# Sheet1.net
KiCad netlist of a schematic drawn in Altium Designer
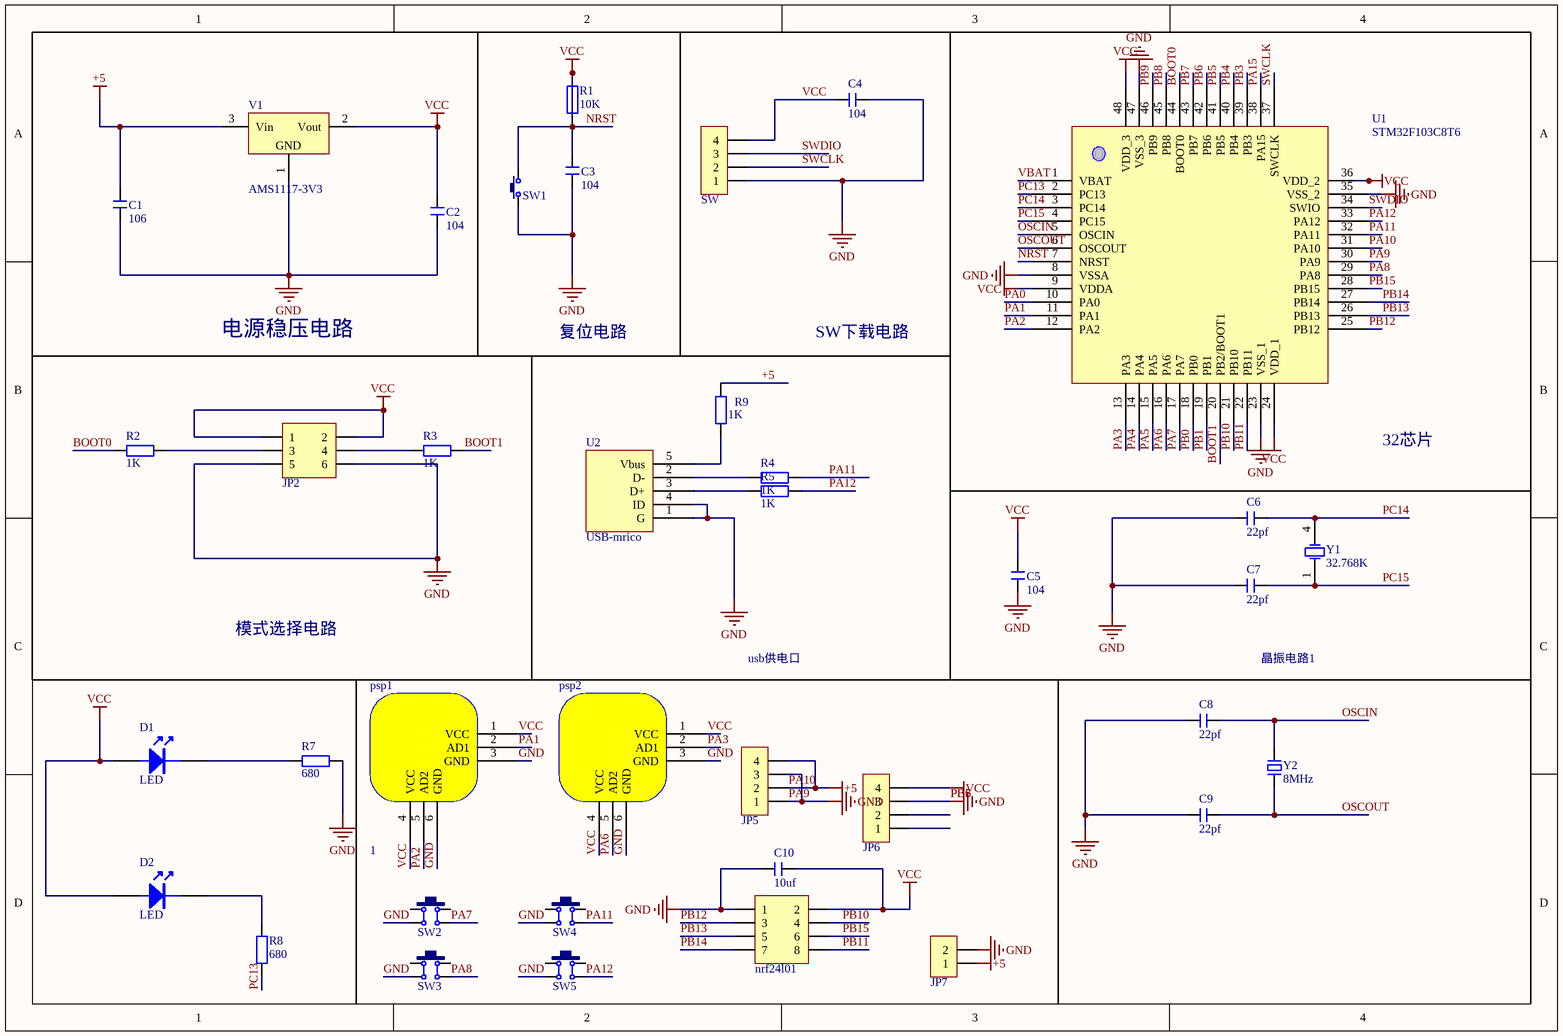
[diagram p0: Sheet1.SchDoc]

(export (version "E")
  (design (tool "Eeschema 10.0.6"))
  (components
    (comp (ref "C1")
      (value "106")
      (footprint "C 0805_L")
      (description "贴片电容")
      (libsource (lib "0.1 - 电阻-电容-电感") (part "C"))
    )
    (comp (ref "C2")
      (value "104")
      (footprint "C 0805_L")
      (description "贴片电容")
      (libsource (lib "0.1 - 电阻-电容-电感") (part "C"))
    )
    (comp (ref "C3")
      (value "104")
      (footprint "C 0805_L")
      (description "贴片电容")
      (libsource (lib "0.1 - 电阻-电容-电感") (part "C"))
    )
    (comp (ref "C4")
      (value "104")
      (footprint "C 0805_L")
      (description "贴片电容")
      (libsource (lib "0.1 - 电阻-电容-电感") (part "C"))
    )
    (comp (ref "C5")
      (value "104")
      (footprint "C 0805_L")
      (description "贴片电容")
      (libsource (lib "0.1 - 电阻-电容-电感") (part "C"))
    )
    (comp (ref "C6")
      (value "22pf")
      (footprint "C 0805_L")
      (description "贴片电容")
      (libsource (lib "0.1 - 电阻-电容-电感") (part "C"))
    )
    (comp (ref "C7")
      (value "22pf")
      (footprint "C 0805_L")
      (description "贴片电容")
      (libsource (lib "0.1 - 电阻-电容-电感") (part "C"))
    )
    (comp (ref "C8")
      (value "22pf")
      (footprint "C 0805_L")
      (description "贴片电容")
      (libsource (lib "0.1 - 电阻-电容-电感") (part "C"))
    )
    (comp (ref "C9")
      (value "22pf")
      (footprint "C 0805_L")
      (description "贴片电容")
      (libsource (lib "0.1 - 电阻-电容-电感") (part "C"))
    )
    (comp (ref "C10")
      (value "10uf")
      (footprint "C 0805_L")
      (description "贴片电容")
      (libsource (lib "0.1 - 电阻-电容-电感") (part "C"))
    )
    (comp (ref "D1") (value "LED") (footprint "LED 0805G") (libsource (lib "stm32原理图库") (part "LED")))
    (comp (ref "D2") (value "LED") (footprint "LED 0805G") (libsource (lib "stm32原理图库") (part "LED")))
    (comp (ref "JP2")
      (value "Header3X2")
      (footprint "HDR2.54-LI-2x3P")
      (description "3*2P接插件")
      (fields (field (name "版权归属") "封装库来自淘宝 ID：黄晶宝石"))
      (libsource (lib "5.3 - 接插件-脚距2.54 (100mil) ") (part "Header 3X2"))
    )
    (comp (ref "JP5")
      (value "HDR-1X4")
      (footprint "HDR2.54-M-LI-4P")
      (description "4P接插件")
      (fields (field (name "版权归属") "封装库来自淘宝 ID：黄晶宝石"))
      (libsource (lib "5.3 - 接插件-脚距2.54 (100mil) ") (part "Header 4"))
    )
    (comp (ref "JP6")
      (value "HDR-1X4")
      (footprint "HDR2.54-M-LI-4P")
      (description "4P接插件")
      (fields (field (name "版权归属") "封装库来自淘宝 ID：黄晶宝石"))
      (libsource (lib "5.3 - 接插件-脚距2.54 (100mil) ") (part "Header 4"))
    )
    (comp (ref "JP7")
      (value "HDR-1X2")
      (footprint "HDR2.54-WI-2P")
      (description "2P接插件")
      (fields (field (name "版权归属") "封装库来自淘宝 ID：黄晶宝石"))
      (libsource (lib "5.3 - 接插件-脚距2.54 (100mil) ") (part "Header 2"))
    )
    (comp (ref "nrf24l01")
      (value "Header 4X2")
      (footprint "HDR2.54-LI-2x4P")
      (description "4*2P接插件")
      (fields (field (name "版权归属") "封装库来自淘宝 ID：黄晶宝石"))
      (libsource (lib "5.3 - 接插件-脚距2.54 (100mil) ") (part "Header 4X2"))
    )
    (comp (ref "psp1") (value "1") (footprint "PSP摇杆") (libsource (lib "PSP摇杆") (part "PSP摇杆")))
    (comp (ref "psp2") (value "~") (footprint "PSP摇杆") (libsource (lib "PSP摇杆") (part "PSP摇杆")))
    (comp (ref "R1")
      (value "10K")
      (footprint "R 0805_L")
      (description "贴片电阻")
      (fields (field (name "版权归属") "来自淘宝 ID：黄晶宝石"))
      (libsource (lib "0.1 - 电阻-电容-电感") (part "R"))
    )
    (comp (ref "R2")
      (value "1K")
      (footprint "R 0805_L")
      (description "贴片电阻")
      (fields (field (name "版权归属") "来自淘宝 ID：黄晶宝石"))
      (libsource (lib "0.1 - 电阻-电容-电感") (part "R"))
    )
    (comp (ref "R3")
      (value "1K")
      (footprint "R 0805_L")
      (description "贴片电阻")
      (fields (field (name "版权归属") "来自淘宝 ID：黄晶宝石"))
      (libsource (lib "0.1 - 电阻-电容-电感") (part "R"))
    )
    (comp (ref "R4")
      (value "1K")
      (footprint "R 0805_L")
      (description "贴片电阻")
      (fields (field (name "版权归属") "来自淘宝 ID：黄晶宝石"))
      (libsource (lib "0.1 - 电阻-电容-电感") (part "R"))
    )
    (comp (ref "R5")
      (value "1K")
      (footprint "R 0805_L")
      (description "贴片电阻")
      (fields (field (name "版权归属") "来自淘宝 ID：黄晶宝石"))
      (libsource (lib "0.1 - 电阻-电容-电感") (part "R"))
    )
    (comp (ref "R7")
      (value "680")
      (footprint "R 0805_L")
      (description "贴片电阻")
      (fields (field (name "版权归属") "来自淘宝 ID：黄晶宝石"))
      (libsource (lib "0.1 - 电阻-电容-电感") (part "R"))
    )
    (comp (ref "R8")
      (value "680")
      (footprint "R 0805_L")
      (description "贴片电阻")
      (fields (field (name "版权归属") "来自淘宝 ID：黄晶宝石"))
      (libsource (lib "0.1 - 电阻-电容-电感") (part "R"))
    )
    (comp (ref "R9")
      (value "1K")
      (footprint "R 0805_L")
      (description "贴片电阻")
      (fields (field (name "版权归属") "来自淘宝 ID：黄晶宝石"))
      (libsource (lib "0.1 - 电阻-电容-电感") (part "R"))
    )
    (comp (ref "SW")
      (value "HDR-1X4")
      (footprint "HDR2.54-WI-4P")
      (description "4P接插件")
      (fields (field (name "版权归属") "封装库来自淘宝 ID：黄晶宝石"))
      (libsource (lib "5.3 - 接插件-脚距2.54 (100mil) ") (part "Header 4"))
    )
    (comp (ref "SW1")
      (value "3x6x5")
      (footprint "TSW SMD-3*6*2.5")
      (description "3x6轻触开关")
      (fields (field (name "版权归属") "封装库来自淘宝 ID：黄晶宝石"))
      (libsource (lib "0.7 - 常用按键-开关") (part "TSW 3x6"))
    )
    (comp (ref "SW2")
      (value "6x6x5")
      (footprint "TSW DIP-6*6*6")
      (description "直插6x6轻触开关")
      (fields (field (name "版权归属") "封装库来自淘宝 ID：黄晶宝石"))
      (libsource (lib "0.7 - 常用按键-开关") (part "TSW DIP-6x6"))
    )
    (comp (ref "SW3")
      (value "6x6x5")
      (footprint "TSW DIP-6*6*6")
      (description "直插6x6轻触开关")
      (fields (field (name "版权归属") "封装库来自淘宝 ID：黄晶宝石"))
      (libsource (lib "0.7 - 常用按键-开关") (part "TSW DIP-6x6"))
    )
    (comp (ref "SW4")
      (value "6x6x5")
      (footprint "TSW DIP-6*6*6")
      (description "直插6x6轻触开关")
      (fields (field (name "版权归属") "封装库来自淘宝 ID：黄晶宝石"))
      (libsource (lib "0.7 - 常用按键-开关") (part "TSW DIP-6x6"))
    )
    (comp (ref "SW5")
      (value "6x6x5")
      (footprint "TSW DIP-6*6*6")
      (description "直插6x6轻触开关")
      (fields (field (name "版权归属") "封装库来自淘宝 ID：黄晶宝石"))
      (libsource (lib "0.7 - 常用按键-开关") (part "TSW DIP-6x6"))
    )
    (comp (ref "U1")
      (value "STM32F103C8T6")
      (footprint "TQFP48 7x7_L")
      (libsource (lib "stm32原理图库") (part "STM32F103C8T6"))
    )
    (comp (ref "U2")
      (value "USB-mrico")
      (footprint "USB-micro_B")
      (libsource (lib "stm32原理图库") (part "usb-STM"))
    )
    (comp (ref "V1")
      (value "AMS1117-3V3")
      (footprint "SOT223_L")
      (description "三端稳压芯片")
      (libsource (lib "1.1 - 电源类芯片") (part "AMS1117"))
    )
    (comp (ref "Y1")
      (value "32.768K")
      (footprint "MC-306")
      (fields (field (name "PUBLISHER") "Altium Limited"))
      (libsource (lib "stm32原理图库") (part "XTAL"))
    )
    (comp (ref "Y2")
      (value "8MHz")
      (footprint "OSC HC-49S")
      (description "2脚无源脚晶振")
      (fields (field (name "版权归属") "封装库来自淘宝卖家 ID：黄晶宝石"))
      (libsource (lib "2.0 - 保险丝-晶振-光耦") (part "XTAL-2P"))
    )
  )
  (nets
    (net (code "1") (name "+5") (class "Default")
      (node (ref "C1") (pin "2") (pinfunction "2_2") (pintype "passive"))
      (node (ref "JP5") (pin "2") (pinfunction "2_2") (pintype "passive"))
      (node (ref "JP5") (pin "4") (pinfunction "4_4") (pintype "passive"))
      (node (ref "JP7") (pin "1") (pinfunction "1_1") (pintype "passive"))
      (node (ref "R9") (pin "2") (pinfunction "2_2") (pintype "passive"))
      (node (ref "U1") (pin "31") (pinfunction "PA10_31") (pintype "passive"))
      (node (ref "V1") (pin "3") (pinfunction "Vin_3") (pintype "passive"))
    )
    (net (code "3") (name "/BOOT0") (class "Default")
      (node (ref "R2") (pin "1") (pinfunction "1_1") (pintype "passive"))
      (node (ref "U1") (pin "44") (pinfunction "BOOT0_44") (pintype "passive"))
    )
    (net (code "4") (name "/BOOT1") (class "Default")
      (node (ref "R3") (pin "2") (pinfunction "2_2") (pintype "passive"))
      (node (ref "U1") (pin "20") (pinfunction "PB2/BOOT1_20") (pintype "passive"))
    )
    (net (code "5") (name "/NRST") (class "Default")
      (node (ref "C3") (pin "2") (pinfunction "2_2") (pintype "passive"))
      (node (ref "R1") (pin "1") (pinfunction "1_1") (pintype "passive"))
      (node (ref "SW1") (pin "2") (pinfunction "2_2") (pintype "passive"))
      (node (ref "U1") (pin "7") (pinfunction "NRST_7") (pintype "passive"))
    )
    (net (code "6") (name "/OSCIN") (class "Default")
      (node (ref "C8") (pin "2") (pinfunction "2_2") (pintype "passive"))
      (node (ref "U1") (pin "5") (pinfunction "OSCIN_5") (pintype "passive"))
      (node (ref "Y2") (pin "2") (pinfunction "2_2") (pintype "passive"))
    )
    (net (code "7") (name "/OSCOUT") (class "Default")
      (node (ref "C9") (pin "2") (pinfunction "2_2") (pintype "passive"))
      (node (ref "U1") (pin "6") (pinfunction "OSCOUT_6") (pintype "passive"))
      (node (ref "Y2") (pin "1") (pinfunction "1_1") (pintype "passive"))
    )
    (net (code "8") (name "/PA0") (class "Default")
      (node (ref "U1") (pin "10") (pinfunction "PA0_10") (pintype "passive"))
    )
    (net (code "9") (name "/PA1") (class "Default")
      (node (ref "U1") (pin "11") (pinfunction "PA1_11") (pintype "passive"))
      (node (ref "psp1") (pin "2") (pinfunction "AD1_2") (pintype "passive"))
    )
    (net (code "10") (name "/PA2") (class "Default")
      (node (ref "U1") (pin "12") (pinfunction "PA2_12") (pintype "passive"))
      (node (ref "psp1") (pin "5") (pinfunction "AD2_5") (pintype "passive"))
    )
    (net (code "11") (name "/PA3") (class "Default")
      (node (ref "U1") (pin "13") (pinfunction "PA3_13") (pintype "passive"))
      (node (ref "psp2") (pin "2") (pinfunction "AD1_2") (pintype "passive"))
    )
    (net (code "12") (name "/PA4") (class "Default")
      (node (ref "U1") (pin "14") (pinfunction "PA4_14") (pintype "passive"))
    )
    (net (code "13") (name "/PA5") (class "Default")
      (node (ref "U1") (pin "15") (pinfunction "PA5_15") (pintype "passive"))
    )
    (net (code "14") (name "/PA6") (class "Default")
      (node (ref "U1") (pin "16") (pinfunction "PA6_16") (pintype "passive"))
      (node (ref "psp2") (pin "5") (pinfunction "AD2_5") (pintype "passive"))
    )
    (net (code "15") (name "/PA7") (class "Default")
      (node (ref "SW2") (pin "3") (pinfunction "3_3") (pintype "passive"))
      (node (ref "U1") (pin "17") (pinfunction "PA7_17") (pintype "passive"))
    )
    (net (code "16") (name "/PA8") (class "Default")
      (node (ref "SW3") (pin "3") (pinfunction "3_3") (pintype "passive"))
      (node (ref "U1") (pin "29") (pinfunction "PA8_29") (pintype "passive"))
    )
    (net (code "17") (name "/PA11") (class "Default")
      (node (ref "R4") (pin "2") (pinfunction "2_2") (pintype "passive"))
      (node (ref "SW4") (pin "3") (pinfunction "3_3") (pintype "passive"))
      (node (ref "U1") (pin "32") (pinfunction "PA11_32") (pintype "passive"))
    )
    (net (code "18") (name "/PA12") (class "Default")
      (node (ref "R5") (pin "2") (pinfunction "2_2") (pintype "passive"))
      (node (ref "SW5") (pin "3") (pinfunction "3_3") (pintype "passive"))
      (node (ref "U1") (pin "33") (pinfunction "PA12_33") (pintype "passive"))
    )
    (net (code "19") (name "/PA15") (class "Default")
      (node (ref "U1") (pin "38") (pinfunction "PA15_38") (pintype "passive"))
    )
    (net (code "20") (name "/PB0") (class "Default")
      (node (ref "U1") (pin "18") (pinfunction "PB0_18") (pintype "passive"))
    )
    (net (code "21") (name "/PB1") (class "Default")
      (node (ref "U1") (pin "19") (pinfunction "PB1_19") (pintype "passive"))
    )
    (net (code "22") (name "/PB3") (class "Default")
      (node (ref "U1") (pin "39") (pinfunction "PB3_39") (pintype "passive"))
    )
    (net (code "23") (name "/PB4") (class "Default")
      (node (ref "U1") (pin "40") (pinfunction "PB4_40") (pintype "passive"))
    )
    (net (code "24") (name "/PB7") (class "Default")
      (node (ref "U1") (pin "43") (pinfunction "PB7_43") (pintype "passive"))
    )
    (net (code "25") (name "/PB8") (class "Default")
      (node (ref "U1") (pin "45") (pinfunction "PB8_45") (pintype "passive"))
    )
    (net (code "26") (name "/PB9") (class "Default")
      (node (ref "U1") (pin "46") (pinfunction "PB9_46") (pintype "passive"))
    )
    (net (code "27") (name "/PB10") (class "Default")
      (node (ref "U1") (pin "21") (pinfunction "PB10_21") (pintype "passive"))
      (node (ref "nrf24l01") (pin "4") (pinfunction "4_4") (pintype "passive"))
    )
    (net (code "28") (name "/PB11") (class "Default")
      (node (ref "U1") (pin "22") (pinfunction "PB11_22") (pintype "passive"))
      (node (ref "nrf24l01") (pin "8") (pinfunction "8_8") (pintype "passive"))
    )
    (net (code "29") (name "/PB12") (class "Default")
      (node (ref "U1") (pin "25") (pinfunction "PB12_25") (pintype "passive"))
      (node (ref "nrf24l01") (pin "3") (pinfunction "3_3") (pintype "passive"))
    )
    (net (code "30") (name "/PB13") (class "Default")
      (node (ref "U1") (pin "26") (pinfunction "PB13_26") (pintype "passive"))
      (node (ref "nrf24l01") (pin "5") (pinfunction "5_5") (pintype "passive"))
    )
    (net (code "31") (name "/PB14") (class "Default")
      (node (ref "U1") (pin "27") (pinfunction "PB14_27") (pintype "passive"))
      (node (ref "nrf24l01") (pin "7") (pinfunction "7_7") (pintype "passive"))
    )
    (net (code "32") (name "/PB15") (class "Default")
      (node (ref "U1") (pin "28") (pinfunction "PB15_28") (pintype "passive"))
      (node (ref "nrf24l01") (pin "6") (pinfunction "6_6") (pintype "passive"))
    )
    (net (code "33") (name "/PC13") (class "Default")
      (node (ref "R8") (pin "2") (pinfunction "2_2") (pintype "passive"))
      (node (ref "U1") (pin "2") (pinfunction "PC13_2") (pintype "passive"))
    )
    (net (code "34") (name "/PC14") (class "Default")
      (node (ref "C6") (pin "1") (pinfunction "1_1") (pintype "passive"))
      (node (ref "U1") (pin "3") (pinfunction "PC14_3") (pintype "passive"))
      (node (ref "Y1") (pin "4") (pinfunction "OSC2_4") (pintype "passive"))
    )
    (net (code "35") (name "/PC15") (class "Default")
      (node (ref "C7") (pin "1") (pinfunction "1_1") (pintype "passive"))
      (node (ref "U1") (pin "4") (pinfunction "PC15_4") (pintype "passive"))
      (node (ref "Y1") (pin "1") (pinfunction "OSC1_1") (pintype "passive"))
    )
    (net (code "36") (name "/SWCLK") (class "Default")
      (node (ref "SW") (pin "2") (pinfunction "2_2") (pintype "passive"))
      (node (ref "U1") (pin "37") (pinfunction "SWCLK_37") (pintype "passive"))
    )
    (net (code "37") (name "/SWDIO") (class "Default")
      (node (ref "SW") (pin "3") (pinfunction "3_3") (pintype "passive"))
      (node (ref "U1") (pin "34") (pinfunction "SWIO_34") (pintype "passive"))
    )
    (net (code "38") (name "/VBAT") (class "Default")
      (node (ref "U1") (pin "1") (pinfunction "VBAT_1") (pintype "passive"))
    )
    (net (code "39") (name "GND") (class "Default")
      (node (ref "C1") (pin "1") (pinfunction "1_1") (pintype "passive"))
      (node (ref "C10") (pin "1") (pinfunction "1_1") (pintype "passive"))
      (node (ref "C2") (pin "1") (pinfunction "1_1") (pintype "passive"))
      (node (ref "C3") (pin "1") (pinfunction "1_1") (pintype "passive"))
      (node (ref "C4") (pin "1") (pinfunction "1_1") (pintype "passive"))
      (node (ref "C5") (pin "1") (pinfunction "1_1") (pintype "passive"))
      (node (ref "C6") (pin "2") (pinfunction "2_2") (pintype "passive"))
      (node (ref "C7") (pin "2") (pinfunction "2_2") (pintype "passive"))
      (node (ref "C8") (pin "1") (pinfunction "1_1") (pintype "passive"))
      (node (ref "C9") (pin "1") (pinfunction "1_1") (pintype "passive"))
      (node (ref "JP2") (pin "5") (pinfunction "5_5") (pintype "passive"))
      (node (ref "JP2") (pin "6") (pinfunction "6_6") (pintype "passive"))
      (node (ref "JP5") (pin "1") (pinfunction "1_1") (pintype "passive"))
      (node (ref "JP5") (pin "3") (pinfunction "3_3") (pintype "passive"))
      (node (ref "JP6") (pin "3") (pinfunction "3_3") (pintype "passive"))
      (node (ref "JP7") (pin "2") (pinfunction "2_2") (pintype "passive"))
      (node (ref "R7") (pin "1") (pinfunction "1_1") (pintype "passive"))
      (node (ref "SW") (pin "1") (pinfunction "1_1") (pintype "passive"))
      (node (ref "SW1") (pin "1") (pinfunction "1_1") (pintype "passive"))
      (node (ref "SW2") (pin "4") (pinfunction "4_4") (pintype "passive"))
      (node (ref "SW3") (pin "4") (pinfunction "4_4") (pintype "passive"))
      (node (ref "SW4") (pin "4") (pinfunction "4_4") (pintype "passive"))
      (node (ref "SW5") (pin "4") (pinfunction "4_4") (pintype "passive"))
      (node (ref "U1") (pin "23") (pinfunction "VSS_1_23") (pintype "passive"))
      (node (ref "U1") (pin "30") (pinfunction "PA9_30") (pintype "passive"))
      (node (ref "U1") (pin "35") (pinfunction "VSS_2_35") (pintype "passive"))
      (node (ref "U1") (pin "41") (pinfunction "PB5_41") (pintype "passive"))
      (node (ref "U1") (pin "42") (pinfunction "PB6_42") (pintype "passive"))
      (node (ref "U1") (pin "47") (pinfunction "VSS_3_47") (pintype "passive"))
      (node (ref "U1") (pin "8") (pinfunction "VSSA_8") (pintype "passive"))
      (node (ref "U2") (pin "1") (pinfunction "G_1") (pintype "passive"))
      (node (ref "U2") (pin "4") (pinfunction "ID_4") (pintype "passive"))
      (node (ref "V1") (pin "1") (pinfunction "GND_1") (pintype "passive"))
      (node (ref "nrf24l01") (pin "1") (pinfunction "1_1") (pintype "passive"))
      (node (ref "psp1") (pin "3") (pinfunction "GND_3") (pintype "passive"))
      (node (ref "psp1") (pin "6") (pinfunction "GND_6") (pintype "passive"))
      (node (ref "psp2") (pin "3") (pinfunction "GND_3") (pintype "passive"))
      (node (ref "psp2") (pin "6") (pinfunction "GND_6") (pintype "passive"))
    )
    (net (code "40") (name "Net-(D1-Pad2)") (class "Default")
      (node (ref "D1") (pin "2") (pinfunction "2_2") (pintype "passive"))
      (node (ref "R7") (pin "2") (pinfunction "2_2") (pintype "passive"))
    )
    (net (code "41") (name "Net-(D2-Pad2)") (class "Default")
      (node (ref "D2") (pin "2") (pinfunction "2_2") (pintype "passive"))
      (node (ref "R8") (pin "1") (pinfunction "1_1") (pintype "passive"))
    )
    (net (code "42") (name "Net-(JP2-Pad3)") (class "Default")
      (node (ref "JP2") (pin "3") (pinfunction "3_3") (pintype "passive"))
      (node (ref "R2") (pin "2") (pinfunction "2_2") (pintype "passive"))
    )
    (net (code "43") (name "Net-(JP2-Pad4)") (class "Default")
      (node (ref "JP2") (pin "4") (pinfunction "4_4") (pintype "passive"))
      (node (ref "R3") (pin "1") (pinfunction "1_1") (pintype "passive"))
    )
    (net (code "44") (name "Net-(U2-D+)") (class "Default")
      (node (ref "R5") (pin "1") (pinfunction "1_1") (pintype "passive"))
      (node (ref "U2") (pin "3") (pinfunction "D+_3") (pintype "passive"))
    )
    (net (code "45") (name "Net-(U2-D-)") (class "Default")
      (node (ref "R4") (pin "1") (pinfunction "1_1") (pintype "passive"))
      (node (ref "U2") (pin "2") (pinfunction "D-_2") (pintype "passive"))
    )
    (net (code "46") (name "Net-(U2-Vbus)") (class "Default")
      (node (ref "R9") (pin "1") (pinfunction "1_1") (pintype "passive"))
      (node (ref "U2") (pin "5") (pinfunction "Vbus_5") (pintype "passive"))
    )
    (net (code "47") (name "VCC") (class "Default")
      (node (ref "C10") (pin "2") (pinfunction "2_2") (pintype "passive"))
      (node (ref "C2") (pin "2") (pinfunction "2_2") (pintype "passive"))
      (node (ref "C4") (pin "2") (pinfunction "2_2") (pintype "passive"))
      (node (ref "C5") (pin "2") (pinfunction "2_2") (pintype "passive"))
      (node (ref "D1") (pin "1") (pinfunction "1_1") (pintype "passive"))
      (node (ref "D2") (pin "1") (pinfunction "1_1") (pintype "passive"))
      (node (ref "JP2") (pin "1") (pinfunction "1_1") (pintype "passive"))
      (node (ref "JP2") (pin "2") (pinfunction "2_2") (pintype "passive"))
      (node (ref "JP6") (pin "4") (pinfunction "4_4") (pintype "passive"))
      (node (ref "R1") (pin "2") (pinfunction "2_2") (pintype "passive"))
      (node (ref "SW") (pin "4") (pinfunction "4_4") (pintype "passive"))
      (node (ref "U1") (pin "24") (pinfunction "VDD_1_24") (pintype "passive"))
      (node (ref "U1") (pin "36") (pinfunction "VDD_2_36") (pintype "passive"))
      (node (ref "U1") (pin "48") (pinfunction "VDD_3_48") (pintype "passive"))
      (node (ref "U1") (pin "9") (pinfunction "VDDA_9") (pintype "passive"))
      (node (ref "V1") (pin "2") (pinfunction "Vout_2") (pintype "passive"))
      (node (ref "nrf24l01") (pin "2") (pinfunction "2_2") (pintype "passive"))
      (node (ref "psp1") (pin "1") (pinfunction "VCC_1") (pintype "passive"))
      (node (ref "psp1") (pin "4") (pinfunction "VCC_4") (pintype "passive"))
      (node (ref "psp2") (pin "1") (pinfunction "VCC_1") (pintype "passive"))
      (node (ref "psp2") (pin "4") (pinfunction "VCC_4") (pintype "passive"))
    )
    (net (code "48") (name "unconnected-(JP6-Pad1)") (class "Default")
      (node (ref "JP6") (pin "1") (pinfunction "1_1") (pintype "passive"))
    )
    (net (code "49") (name "unconnected-(JP6-Pad2)") (class "Default")
      (node (ref "JP6") (pin "2") (pinfunction "2_2") (pintype "passive"))
    )
    (net (code "50") (name "unconnected-(SW2-Pad1)") (class "Default")
      (node (ref "SW2") (pin "1") (pinfunction "1_1") (pintype "passive"))
    )
    (net (code "51") (name "unconnected-(SW2-Pad2)") (class "Default")
      (node (ref "SW2") (pin "2") (pinfunction "2_2") (pintype "passive"))
    )
    (net (code "52") (name "unconnected-(SW3-Pad1)") (class "Default")
      (node (ref "SW3") (pin "1") (pinfunction "1_1") (pintype "passive"))
    )
    (net (code "53") (name "unconnected-(SW3-Pad2)") (class "Default")
      (node (ref "SW3") (pin "2") (pinfunction "2_2") (pintype "passive"))
    )
    (net (code "54") (name "unconnected-(SW4-Pad1)") (class "Default")
      (node (ref "SW4") (pin "1") (pinfunction "1_1") (pintype "passive"))
    )
    (net (code "55") (name "unconnected-(SW4-Pad2)") (class "Default")
      (node (ref "SW4") (pin "2") (pinfunction "2_2") (pintype "passive"))
    )
    (net (code "56") (name "unconnected-(SW5-Pad1)") (class "Default")
      (node (ref "SW5") (pin "1") (pinfunction "1_1") (pintype "passive"))
    )
    (net (code "57") (name "unconnected-(SW5-Pad2)") (class "Default")
      (node (ref "SW5") (pin "2") (pinfunction "2_2") (pintype "passive"))
    )
  )
)
